# Sigfox_Pico.net
KiCad netlist of a schematic drawn in EAGLE
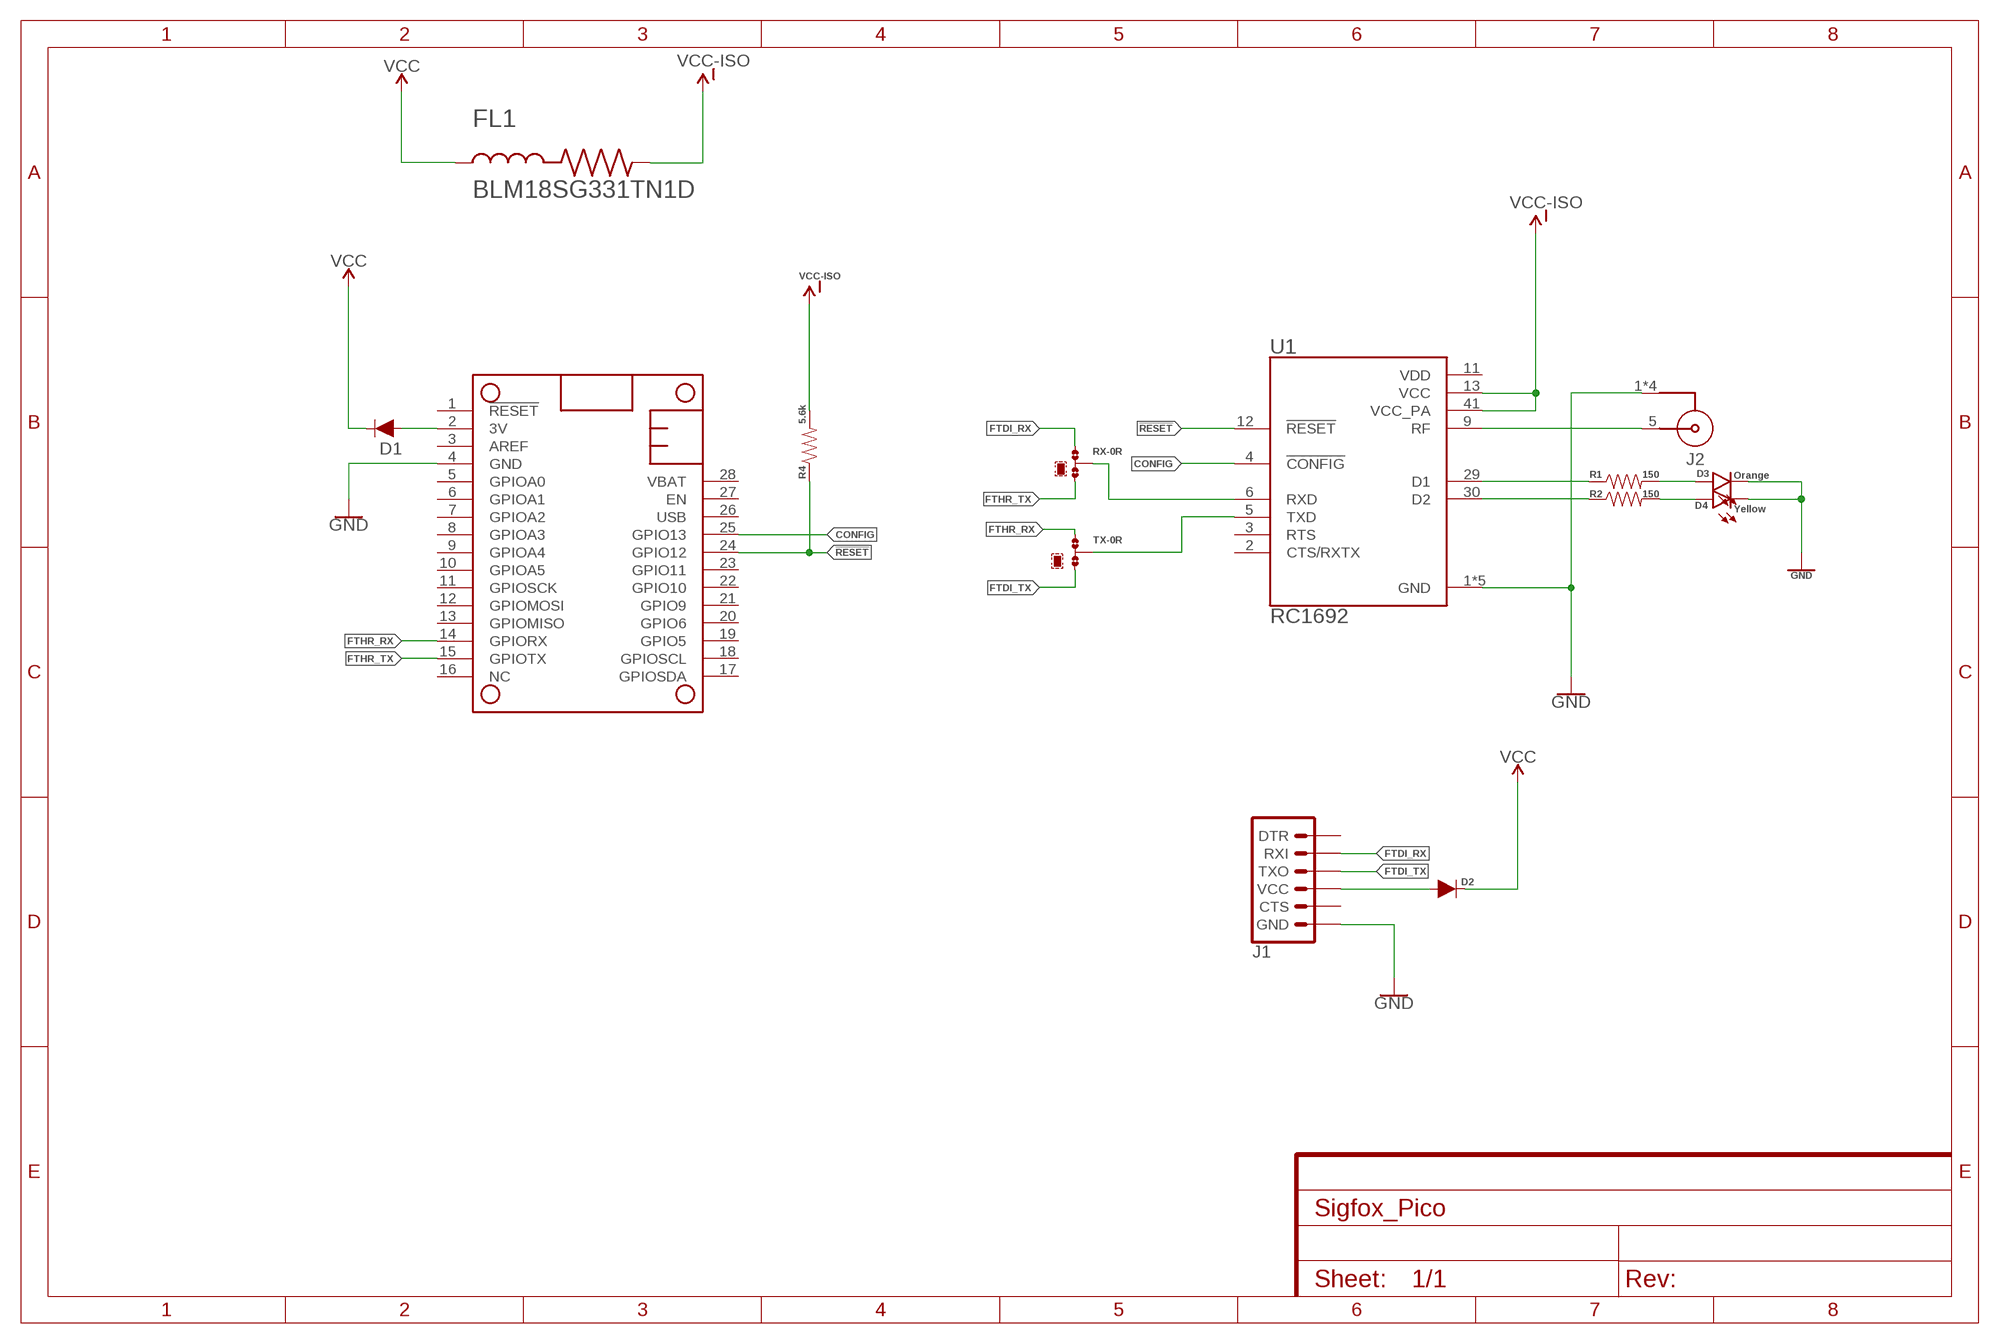
[diagram p0: schematic, sheet 1]

(export (version "E")
  (design (tool "Eeschema 10.0.6"))
  (components
    (comp (ref "D1")
      (value "250mA/100V")
      (footprint "eagle-import:SOD-323")
      (libsource (lib "eagle-import") (part "DIODE-BAS16J"))
    )
    (comp (ref "D2")
      (value "250mA/100V")
      (footprint "eagle-import:SOD-323")
      (libsource (lib "eagle-import") (part "DIODE-BAS16J"))
    )
    (comp (ref "D3")
      (value "Orange")
      (footprint "eagle-import:LED-0603")
      (libsource (lib "eagle-import") (part "LED-YELLOW0603"))
    )
    (comp (ref "D4")
      (value "Yellow")
      (footprint "eagle-import:LED-0603")
      (libsource (lib "eagle-import") (part "LED-YELLOW0603"))
    )
    (comp (ref "FL1")
      (value "BLM18SG331TN1D")
      (footprint "eagle-import:BEADC1608X65N")
      (fields (field (name "MF") "Murata Electronics"))
      (libsource (lib "eagle-import") (part "BLM18SG331TN1D"))
    )
    (comp (ref "J1")
      (value "6_PIN_SERIAL_TARGETSILK")
      (footprint "eagle-import:6_PIN_SERIAL_TARGET_SIDE_W_SILK")
      (libsource (lib "eagle-import") (part "6_PIN_SERIAL_TARGETSILK"))
    )
    (comp (ref "J2")
      (value "63012002124503")
      (footprint "eagle-import:63012002124503")
      (fields
        (field (name "DIGI-KEY_PART_NUMBER") "732-13860-ND")
        (field (name "MF") "Wurth Electronics Inc.")
      )
      (libsource (lib "eagle-import") (part "63012002124503"))
    )
    (comp (ref "MS1")
      (value "FEATHERWING")
      (footprint "eagle-import:FEATHERWING")
      (libsource (lib "eagle-import") (part "FEATHERWING"))
    )
    (comp (ref "R1")
      (value "150")
      (footprint "eagle-import:0603")
      (libsource (lib "eagle-import") (part "150OHM-0603-1/10W-1%"))
    )
    (comp (ref "R2")
      (value "150")
      (footprint "eagle-import:0603")
      (libsource (lib "eagle-import") (part "150OHM-0603-1/10W-1%"))
    )
    (comp (ref "R4")
      (value "5.6k")
      (footprint "eagle-import:0603")
      (libsource (lib "eagle-import") (part "5.6KOHM-0603-1/10W-1%"))
    )
    (comp (ref "RX")
      (value "0R-JUMPB")
      (footprint "eagle-import:B0R-JMP")
      (libsource (lib "eagle-import") (part "0R-JUMPB"))
    )
    (comp (ref "TX")
      (value "0R-JUMPB")
      (footprint "eagle-import:B0R-JMP")
      (libsource (lib "eagle-import") (part "0R-JUMPB"))
    )
    (comp (ref "U1")
      (value "RC1692")
      (footprint "eagle-import:MODULE_RC1682-SIG")
      (fields (field (name "MF") "Radiocrafts AS") (field (name "MP") "RC1682-SIG"))
      (libsource (lib "eagle-import") (part "RC1692"))
    )
  )
  (nets
    (net (code "1") (name "/USB") (class "Default")
      (node (ref "MS1") (pin "26") (pinfunction "USB_26") (pintype "power_in"))
    )
    (net (code "2") (name "/VBAT") (class "Default")
      (node (ref "MS1") (pin "28") (pinfunction "VBAT_28") (pintype "power_in"))
    )
    (net (code "3") (name "/VDD") (class "Default")
      (node (ref "U1") (pin "11") (pinfunction "VDD_11") (pintype "power_in"))
    )
    (net (code "4") (name "/~{RESET}") (class "Default")
      (node (ref "MS1") (pin "24") (pinfunction "GPIO12_24") (pintype "bidirectional"))
      (node (ref "R4") (pin "1") (pinfunction "1_1") (pintype "passive"))
      (node (ref "U1") (pin "12") (pinfunction "~{RESET}_12") (pintype "input"))
    )
    (net (code "5") (name "CONFIG") (class "Default")
      (node (ref "MS1") (pin "25") (pinfunction "GPIO13_25") (pintype "bidirectional"))
      (node (ref "U1") (pin "4") (pinfunction "~{CONFIG}_4") (pintype "input"))
    )
    (net (code "6") (name "FTDI_RX") (class "Default")
      (node (ref "J1") (pin "P$3") (pinfunction "RXI_P$3") (pintype "passive"))
      (node (ref "RX") (pin "1") (pinfunction "1_1") (pintype "passive"))
    )
    (net (code "7") (name "FTDI_TX") (class "Default")
      (node (ref "J1") (pin "P$2") (pinfunction "TXO_P$2") (pintype "passive"))
      (node (ref "TX") (pin "3") (pinfunction "3_3") (pintype "passive"))
    )
    (net (code "8") (name "FTHR_RX") (class "Default")
      (node (ref "MS1") (pin "14") (pinfunction "GPIORX_14") (pintype "bidirectional"))
      (node (ref "TX") (pin "1") (pinfunction "1_1") (pintype "passive"))
    )
    (net (code "9") (name "FTHR_TX") (class "Default")
      (node (ref "MS1") (pin "15") (pinfunction "GPIOTX_15") (pintype "bidirectional"))
      (node (ref "RX") (pin "3") (pinfunction "3_3") (pintype "passive"))
    )
    (net (code "10") (name "GND") (class "Default")
      (node (ref "D3") (pin "C") (pinfunction "C_C") (pintype "passive"))
      (node (ref "D4") (pin "C") (pinfunction "C_C") (pintype "passive"))
      (node (ref "J1") (pin "P$6") (pinfunction "GND_P$6") (pintype "passive"))
      (node (ref "J2") (pin "1") (pinfunction "2_1") (pintype "passive"))
      (node (ref "J2") (pin "2") (pinfunction "2_2") (pintype "passive"))
      (node (ref "J2") (pin "3") (pinfunction "2_3") (pintype "passive"))
      (node (ref "J2") (pin "4") (pinfunction "2_4") (pintype "passive"))
      (node (ref "MS1") (pin "4") (pinfunction "GND_4") (pintype "power_in"))
      (node (ref "U1") (pin "1") (pinfunction "GND_1") (pintype "power_in"))
      (node (ref "U1") (pin "10") (pinfunction "GND_10") (pintype "power_in"))
      (node (ref "U1") (pin "14") (pinfunction "GND_14") (pintype "power_in"))
      (node (ref "U1") (pin "7") (pinfunction "GND_7") (pintype "power_in"))
      (node (ref "U1") (pin "8") (pinfunction "GND_8") (pintype "power_in"))
    )
    (net (code "11") (name "Net-(D3-PadA)") (class "Default")
      (node (ref "D3") (pin "A") (pinfunction "A_A") (pintype "passive"))
      (node (ref "R1") (pin "2") (pinfunction "2_2") (pintype "passive"))
    )
    (net (code "12") (name "Net-(D4-PadA)") (class "Default")
      (node (ref "D4") (pin "A") (pinfunction "A_A") (pintype "passive"))
      (node (ref "R2") (pin "2") (pinfunction "2_2") (pintype "passive"))
    )
    (net (code "13") (name "Net-(J1-VCC)") (class "Default")
      (node (ref "D2") (pin "A") (pinfunction "A_A") (pintype "passive"))
      (node (ref "J1") (pin "P$4") (pinfunction "VCC_P$4") (pintype "passive"))
    )
    (net (code "14") (name "Net-(J2-1)") (class "Default")
      (node (ref "J2") (pin "5") (pinfunction "1_5") (pintype "passive"))
      (node (ref "U1") (pin "9") (pinfunction "RF_9") (pintype "bidirectional"))
    )
    (net (code "15") (name "Net-(MS1-3V)") (class "Default")
      (node (ref "D1") (pin "A") (pinfunction "A_A") (pintype "passive"))
      (node (ref "MS1") (pin "2") (pinfunction "3V_2") (pintype "power_in"))
    )
    (net (code "16") (name "Net-(U1-D1)") (class "Default")
      (node (ref "R1") (pin "1") (pinfunction "1_1") (pintype "passive"))
      (node (ref "U1") (pin "29") (pinfunction "D1_29") (pintype "bidirectional"))
    )
    (net (code "17") (name "Net-(U1-D2)") (class "Default")
      (node (ref "R2") (pin "1") (pinfunction "1_1") (pintype "passive"))
      (node (ref "U1") (pin "30") (pinfunction "D2_30") (pintype "bidirectional"))
    )
    (net (code "18") (name "Net-(U1-RXD)") (class "Default")
      (node (ref "RX") (pin "2") (pinfunction "2_2") (pintype "passive"))
      (node (ref "U1") (pin "6") (pinfunction "RXD_6") (pintype "input"))
    )
    (net (code "19") (name "Net-(U1-TXD)") (class "Default")
      (node (ref "TX") (pin "2") (pinfunction "2_2") (pintype "passive"))
      (node (ref "U1") (pin "5") (pinfunction "TXD_5") (pintype "output"))
    )
    (net (code "20") (name "VCC") (class "Default")
      (node (ref "D1") (pin "C") (pinfunction "C_C") (pintype "passive"))
      (node (ref "D2") (pin "C") (pinfunction "C_C") (pintype "passive"))
      (node (ref "FL1") (pin "1") (pinfunction "1_1") (pintype "passive"))
    )
    (net (code "21") (name "VCC-ISO") (class "Default")
      (node (ref "FL1") (pin "2") (pinfunction "2_2") (pintype "passive"))
      (node (ref "R4") (pin "2") (pinfunction "2_2") (pintype "passive"))
      (node (ref "U1") (pin "13") (pinfunction "VCC_13") (pintype "power_in"))
      (node (ref "U1") (pin "41") (pinfunction "VCC_PA_41") (pintype "power_in"))
    )
    (net (code "22") (name "unconnected-(J1-CTS-PadP$5)") (class "Default")
      (node (ref "J1") (pin "P$5") (pinfunction "CTS_P$5") (pintype "passive"))
    )
    (net (code "23") (name "unconnected-(J1-DTR-PadP$1)") (class "Default")
      (node (ref "J1") (pin "P$1") (pinfunction "DTR_P$1") (pintype "passive"))
    )
    (net (code "24") (name "unconnected-(MS1-AREF-Pad3)") (class "Default")
      (node (ref "MS1") (pin "3") (pinfunction "AREF_3") (pintype "passive"))
    )
    (net (code "25") (name "unconnected-(MS1-EN-Pad27)") (class "Default")
      (node (ref "MS1") (pin "27") (pinfunction "EN_27") (pintype "passive"))
    )
    (net (code "26") (name "unconnected-(MS1-GPIO5-Pad19)") (class "Default")
      (node (ref "MS1") (pin "19") (pinfunction "GPIO5_19") (pintype "bidirectional"))
    )
    (net (code "27") (name "unconnected-(MS1-GPIO6-Pad20)") (class "Default")
      (node (ref "MS1") (pin "20") (pinfunction "GPIO6_20") (pintype "bidirectional"))
    )
    (net (code "28") (name "unconnected-(MS1-GPIO9-Pad21)") (class "Default")
      (node (ref "MS1") (pin "21") (pinfunction "GPIO9_21") (pintype "bidirectional"))
    )
    (net (code "29") (name "unconnected-(MS1-GPIO10-Pad22)") (class "Default")
      (node (ref "MS1") (pin "22") (pinfunction "GPIO10_22") (pintype "bidirectional"))
    )
    (net (code "30") (name "unconnected-(MS1-GPIO11-Pad23)") (class "Default")
      (node (ref "MS1") (pin "23") (pinfunction "GPIO11_23") (pintype "bidirectional"))
    )
    (net (code "31") (name "unconnected-(MS1-GPIOA0-Pad5)") (class "Default")
      (node (ref "MS1") (pin "5") (pinfunction "GPIOA0_5") (pintype "bidirectional"))
    )
    (net (code "32") (name "unconnected-(MS1-GPIOA1-Pad6)") (class "Default")
      (node (ref "MS1") (pin "6") (pinfunction "GPIOA1_6") (pintype "bidirectional"))
    )
    (net (code "33") (name "unconnected-(MS1-GPIOA2-Pad7)") (class "Default")
      (node (ref "MS1") (pin "7") (pinfunction "GPIOA2_7") (pintype "bidirectional"))
    )
    (net (code "34") (name "unconnected-(MS1-GPIOA3-Pad8)") (class "Default")
      (node (ref "MS1") (pin "8") (pinfunction "GPIOA3_8") (pintype "bidirectional"))
    )
    (net (code "35") (name "unconnected-(MS1-GPIOA4-Pad9)") (class "Default")
      (node (ref "MS1") (pin "9") (pinfunction "GPIOA4_9") (pintype "bidirectional"))
    )
    (net (code "36") (name "unconnected-(MS1-GPIOA5-Pad10)") (class "Default")
      (node (ref "MS1") (pin "10") (pinfunction "GPIOA5_10") (pintype "bidirectional"))
    )
    (net (code "37") (name "unconnected-(MS1-GPIOMISO-Pad13)") (class "Default")
      (node (ref "MS1") (pin "13") (pinfunction "GPIOMISO_13") (pintype "bidirectional"))
    )
    (net (code "38") (name "unconnected-(MS1-GPIOMOSI-Pad12)") (class "Default")
      (node (ref "MS1") (pin "12") (pinfunction "GPIOMOSI_12") (pintype "bidirectional"))
    )
    (net (code "39") (name "unconnected-(MS1-GPIOSCK-Pad11)") (class "Default")
      (node (ref "MS1") (pin "11") (pinfunction "GPIOSCK_11") (pintype "bidirectional"))
    )
    (net (code "40") (name "unconnected-(MS1-GPIOSCL-Pad18)") (class "Default")
      (node (ref "MS1") (pin "18") (pinfunction "GPIOSCL_18") (pintype "bidirectional"))
    )
    (net (code "41") (name "unconnected-(MS1-GPIOSDA-Pad17)") (class "Default")
      (node (ref "MS1") (pin "17") (pinfunction "GPIOSDA_17") (pintype "bidirectional"))
    )
    (net (code "42") (name "unconnected-(MS1-NC-Pad16)") (class "Default")
      (node (ref "MS1") (pin "16") (pinfunction "NC_16") (pintype "passive"))
    )
    (net (code "43") (name "unconnected-(MS1-~{RESET}-Pad1)") (class "Default")
      (node (ref "MS1") (pin "1") (pinfunction "~{RESET}_1") (pintype "input"))
    )
    (net (code "44") (name "unconnected-(U1-CTS{slash}RXTX-Pad2)") (class "Default")
      (node (ref "U1") (pin "2") (pinfunction "CTS/RXTX_2") (pintype "bidirectional"))
    )
    (net (code "45") (name "unconnected-(U1-RTS-Pad3)") (class "Default")
      (node (ref "U1") (pin "3") (pinfunction "RTS_3") (pintype "input"))
    )
  )
)
